# ospi_v13.net
KiCad netlist of a schematic drawn in EAGLE
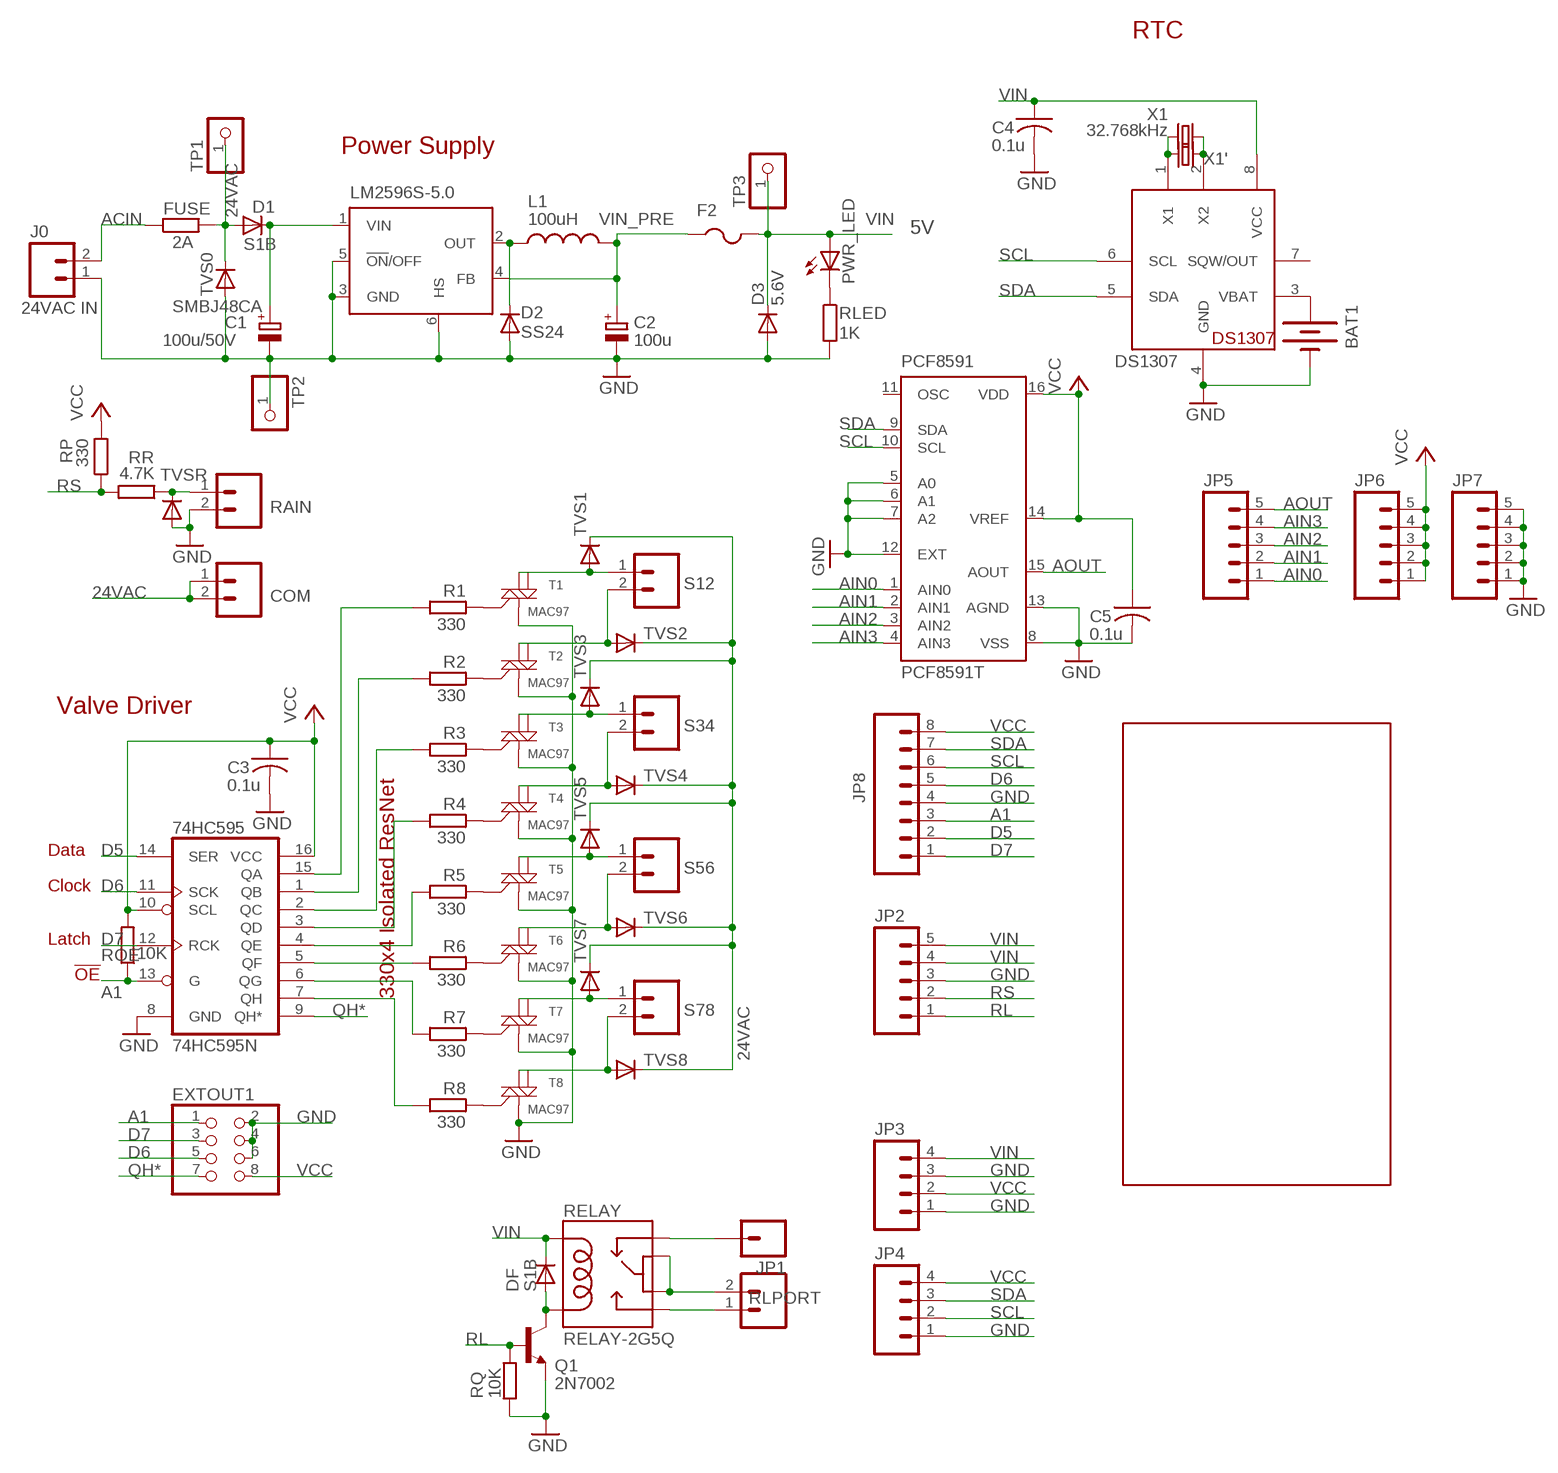
[diagram p0: schematic, sheet 1]

(export (version "E")
  (design (tool "Eeschema 10.0.6"))
  (components
    (comp (ref "74HC595")
      (value "74HC595N")
      (footprint "eagle-import:SO16")
      (libsource (lib "eagle-import") (part "74595DLS"))
    )
    (comp (ref "BAT1")
      (value "BATTERYBATTERY_12MM_SMT")
      (footprint "eagle-import:BATTCON_12MM_SMT")
      (libsource (lib "eagle-import") (part "BATTERYBATTERY_12MM_SMT"))
    )
    (comp (ref "C1")
      (value "100u/50V")
      (footprint "eagle-import:PANASONIC_E")
      (libsource (lib "eagle-import") (part "CPOL-EUE"))
    )
    (comp (ref "C2")
      (value "100u")
      (footprint "eagle-import:PANASONIC_E")
      (libsource (lib "eagle-import") (part "CPOL-EUE"))
    )
    (comp (ref "C3")
      (value "0.1u")
      (footprint "eagle-import:C0805K")
      (libsource (lib "eagle-import") (part "C-USC0805K"))
    )
    (comp (ref "C4")
      (value "0.1u")
      (footprint "eagle-import:C0805K")
      (libsource (lib "eagle-import") (part "C-USC0805K"))
    )
    (comp (ref "C5")
      (value "0.1u")
      (footprint "eagle-import:C0805K")
      (libsource (lib "eagle-import") (part "C-USC0805K"))
    )
    (comp (ref "COM")
      (value "M025MM-X")
      (footprint "eagle-import:SCREWTERMINAL-5MM-2-X")
      (libsource (lib "eagle-import") (part "M025MM-X"))
    )
    (comp (ref "D1")
      (value "S1B")
      (footprint "eagle-import:DO-214AC")
      (libsource (lib "eagle-import") (part "DIODE-DO-214AC"))
    )
    (comp (ref "D2")
      (value "SS24")
      (footprint "eagle-import:DO-214AC")
      (libsource (lib "eagle-import") (part "DIODE-DO-214AC"))
    )
    (comp (ref "D3")
      (value "5.6V")
      (footprint "eagle-import:MINIMELF")
      (libsource (lib "eagle-import") (part "DIODE-MINIMELF"))
    )
    (comp (ref "DF")
      (value "S1B")
      (footprint "eagle-import:DO-214AC")
      (libsource (lib "eagle-import") (part "DIODE-DO-214AC"))
    )
    (comp (ref "DS1307")
      (value "DS1307")
      (footprint "eagle-import:SO08")
      (libsource (lib "eagle-import") (part "DS1307SOIC"))
    )
    (comp (ref "EXTOUT1")
      (value "PINHD-2X4/90")
      (footprint "eagle-import:2X04_90")
      (libsource (lib "eagle-import") (part "PINHD-2X4/90"))
    )
    (comp (ref "F2")
      (value "PTCFUSE-1812")
      (footprint "eagle-import:1812")
      (libsource (lib "eagle-import") (part "PTCFUSE-1812"))
    )
    (comp (ref "FUSE")
      (value "2A")
      (footprint "eagle-import:0411_15")
      (libsource (lib "eagle-import") (part "R-EU_0411/15"))
    )
    (comp (ref "J0")
      (value "24VAC IN")
      (footprint "eagle-import:SCREWTERMINAL-4MM-2-X")
      (libsource (lib "eagle-import") (part "M024MM-X"))
    )
    (comp (ref "JP1")
      (value "M01PTH")
      (footprint "eagle-import:1X01")
      (libsource (lib "eagle-import") (part "M01PTH"))
    )
    (comp (ref "JP2")
      (value "M05LOCK")
      (footprint "eagle-import:1X05_LOCK")
      (libsource (lib "eagle-import") (part "M05LOCK"))
    )
    (comp (ref "JP3")
      (value "M04LOCK")
      (footprint "eagle-import:1X04_LOCK")
      (libsource (lib "eagle-import") (part "M04LOCK"))
    )
    (comp (ref "JP4")
      (value "M04LOCK")
      (footprint "eagle-import:1X04_LOCK")
      (libsource (lib "eagle-import") (part "M04LOCK"))
    )
    (comp (ref "JP5")
      (value "M05LOCK")
      (footprint "eagle-import:1X05_LOCK")
      (libsource (lib "eagle-import") (part "M05LOCK"))
    )
    (comp (ref "JP6")
      (value "M05LOCK")
      (footprint "eagle-import:1X05_LOCK")
      (libsource (lib "eagle-import") (part "M05LOCK"))
    )
    (comp (ref "JP7")
      (value "M05LOCK")
      (footprint "eagle-import:1X05_LOCK")
      (libsource (lib "eagle-import") (part "M05LOCK"))
    )
    (comp (ref "JP8")
      (value "M08LOCK")
      (footprint "eagle-import:1X08_LOCK")
      (libsource (lib "eagle-import") (part "M08LOCK"))
    )
    (comp (ref "L1")
      (value "100uH")
      (footprint "eagle-import:CDRH125")
      (libsource (lib "eagle-import") (part "INDUCTORPWR"))
    )
    (comp (ref "LM2596S-5.0")
      (value "LM2596S")
      (footprint "eagle-import:TO263-5")
      (fields (field (name "MF") "NATIONAL SEMICONDUCTOR") (field (name "MPN") "LM2596S-ADJ/NOPB"))
      (libsource (lib "eagle-import") (part "LM2596S"))
    )
    (comp (ref "PCF8591")
      (value "PCF8591T")
      (footprint "eagle-import:SO16W")
      (fields (field (name "MPN") "PCF8591T/2,512"))
      (libsource (lib "eagle-import") (part "PCF8591T"))
    )
    (comp (ref "PWR_LED")
      (value "LEDCHIPLED_0805")
      (footprint "eagle-import:CHIPLED_0805")
      (libsource (lib "eagle-import") (part "LEDCHIPLED_0805"))
    )
    (comp (ref "Q1")
      (value "2N7002")
      (footprint "eagle-import:SOT23-3")
      (libsource (lib "eagle-import") (part "TRANSISTOR_NPNSOT23-3"))
    )
    (comp (ref "R1")
      (value "330")
      (footprint "eagle-import:R0805")
      (libsource (lib "eagle-import") (part "R-EU_R0805"))
    )
    (comp (ref "R2")
      (value "330")
      (footprint "eagle-import:R0805")
      (libsource (lib "eagle-import") (part "R-EU_R0805"))
    )
    (comp (ref "R3")
      (value "330")
      (footprint "eagle-import:R0805")
      (libsource (lib "eagle-import") (part "R-EU_R0805"))
    )
    (comp (ref "R4")
      (value "330")
      (footprint "eagle-import:R0805")
      (libsource (lib "eagle-import") (part "R-EU_R0805"))
    )
    (comp (ref "R5")
      (value "330")
      (footprint "eagle-import:R0805")
      (libsource (lib "eagle-import") (part "R-EU_R0805"))
    )
    (comp (ref "R6")
      (value "330")
      (footprint "eagle-import:R0805")
      (libsource (lib "eagle-import") (part "R-EU_R0805"))
    )
    (comp (ref "R7")
      (value "330")
      (footprint "eagle-import:R0805")
      (libsource (lib "eagle-import") (part "R-EU_R0805"))
    )
    (comp (ref "R8")
      (value "330")
      (footprint "eagle-import:R0805")
      (libsource (lib "eagle-import") (part "R-EU_R0805"))
    )
    (comp (ref "RAIN")
      (value "M025MM-X")
      (footprint "eagle-import:SCREWTERMINAL-5MM-2-X")
      (libsource (lib "eagle-import") (part "M025MM-X"))
    )
    (comp (ref "RELAY")
      (value "RELAY-2G5Q")
      (footprint "eagle-import:RELAY-G5V")
      (libsource (lib "eagle-import") (part "RELAY-2G5Q"))
    )
    (comp (ref "RLED")
      (value "1K")
      (footprint "eagle-import:R0805")
      (libsource (lib "eagle-import") (part "R-EU_R0805"))
    )
    (comp (ref "RLPORT")
      (value "M025MM")
      (footprint "eagle-import:SCREWTERMINAL-5MM-2")
      (libsource (lib "eagle-import") (part "M025MM"))
    )
    (comp (ref "ROE")
      (value "10K")
      (footprint "eagle-import:R0805")
      (libsource (lib "eagle-import") (part "R-EU_R0805"))
    )
    (comp (ref "RP")
      (value "330")
      (footprint "eagle-import:R0805")
      (libsource (lib "eagle-import") (part "R-EU_R0805"))
    )
    (comp (ref "RQ")
      (value "10K")
      (footprint "eagle-import:R0805")
      (libsource (lib "eagle-import") (part "R-EU_R0805"))
    )
    (comp (ref "RR")
      (value "4.7K")
      (footprint "eagle-import:R0805")
      (libsource (lib "eagle-import") (part "R-EU_R0805"))
    )
    (comp (ref "S12")
      (value "M025MM-X")
      (footprint "eagle-import:SCREWTERMINAL-5MM-2-X")
      (libsource (lib "eagle-import") (part "M025MM-X"))
    )
    (comp (ref "S34")
      (value "M025MM-X")
      (footprint "eagle-import:SCREWTERMINAL-5MM-2-X")
      (libsource (lib "eagle-import") (part "M025MM-X"))
    )
    (comp (ref "S56")
      (value "M025MM-X")
      (footprint "eagle-import:SCREWTERMINAL-5MM-2-X")
      (libsource (lib "eagle-import") (part "M025MM-X"))
    )
    (comp (ref "S78")
      (value "M025MM-X")
      (footprint "eagle-import:SCREWTERMINAL-5MM-2-X")
      (libsource (lib "eagle-import") (part "M025MM-X"))
    )
    (comp (ref "T1")
      (value "MAC97")
      (footprint "eagle-import:SOT223")
      (libsource (lib "eagle-import") (part "MAC97SOT223"))
    )
    (comp (ref "T2")
      (value "MAC97")
      (footprint "eagle-import:SOT223")
      (libsource (lib "eagle-import") (part "MAC97SOT223"))
    )
    (comp (ref "T3")
      (value "MAC97")
      (footprint "eagle-import:SOT223")
      (libsource (lib "eagle-import") (part "MAC97SOT223"))
    )
    (comp (ref "T4")
      (value "MAC97")
      (footprint "eagle-import:SOT223")
      (libsource (lib "eagle-import") (part "MAC97SOT223"))
    )
    (comp (ref "T5")
      (value "MAC97")
      (footprint "eagle-import:SOT223")
      (libsource (lib "eagle-import") (part "MAC97SOT223"))
    )
    (comp (ref "T6")
      (value "MAC97")
      (footprint "eagle-import:SOT223")
      (libsource (lib "eagle-import") (part "MAC97SOT223"))
    )
    (comp (ref "T7")
      (value "MAC97")
      (footprint "eagle-import:SOT223")
      (libsource (lib "eagle-import") (part "MAC97SOT223"))
    )
    (comp (ref "T8")
      (value "MAC97")
      (footprint "eagle-import:SOT223")
      (libsource (lib "eagle-import") (part "MAC97SOT223"))
    )
    (comp (ref "TP1")
      (value "PINHD-1X1CB")
      (footprint "eagle-import:1X01-CLEANBIG")
      (libsource (lib "eagle-import") (part "PINHD-1X1CB"))
    )
    (comp (ref "TP2")
      (value "PINHD-1X1CB")
      (footprint "eagle-import:1X01-CLEANBIG")
      (libsource (lib "eagle-import") (part "PINHD-1X1CB"))
    )
    (comp (ref "TP3")
      (value "PINHD-1X1CB")
      (footprint "eagle-import:1X01-CLEANBIG")
      (libsource (lib "eagle-import") (part "PINHD-1X1CB"))
    )
    (comp (ref "TVS0")
      (value "SMBJ48CA")
      (footprint "eagle-import:SMB")
      (libsource (lib "eagle-import") (part "DIODE-SMB"))
    )
    (comp (ref "TVS1")
      (value "DIODE-SMB")
      (footprint "eagle-import:SMB")
      (libsource (lib "eagle-import") (part "DIODE-SMB"))
    )
    (comp (ref "TVS2")
      (value "DIODE-SMB")
      (footprint "eagle-import:SMB")
      (libsource (lib "eagle-import") (part "DIODE-SMB"))
    )
    (comp (ref "TVS3")
      (value "DIODE-SMB")
      (footprint "eagle-import:SMB")
      (libsource (lib "eagle-import") (part "DIODE-SMB"))
    )
    (comp (ref "TVS4")
      (value "DIODE-SMB")
      (footprint "eagle-import:SMB")
      (libsource (lib "eagle-import") (part "DIODE-SMB"))
    )
    (comp (ref "TVS5")
      (value "DIODE-SMB")
      (footprint "eagle-import:SMB")
      (libsource (lib "eagle-import") (part "DIODE-SMB"))
    )
    (comp (ref "TVS6")
      (value "DIODE-SMB")
      (footprint "eagle-import:SMB")
      (libsource (lib "eagle-import") (part "DIODE-SMB"))
    )
    (comp (ref "TVS7")
      (value "DIODE-SMB")
      (footprint "eagle-import:SMB")
      (libsource (lib "eagle-import") (part "DIODE-SMB"))
    )
    (comp (ref "TVS8")
      (value "DIODE-SMB")
      (footprint "eagle-import:SMB")
      (libsource (lib "eagle-import") (part "DIODE-SMB"))
    )
    (comp (ref "TVSR")
      (value "DIODE-SMB")
      (footprint "eagle-import:SMB")
      (libsource (lib "eagle-import") (part "DIODE-SMB"))
    )
    (comp (ref "U$2")
      (value "OSPI")
      (footprint "eagle-import:OSPI")
      (libsource (lib "eagle-import") (part "OSPI"))
    )
    (comp (ref "X1")
      (value "32.768kHz")
      (footprint "eagle-import:MM20SS")
      (libsource (lib "eagle-import") (part "CRYSTALMM20SS"))
    )
    (comp (ref "X1'")
      (value "32.768kHz")
      (footprint "eagle-import:TC38H")
      (libsource (lib "eagle-import") (part "CRYSTALTC38H"))
    )
  )
  (nets
    (net (code "1") (name "/24VAC") (class "Default")
      (node (ref "COM") (pin "1") (pinfunction "1_1") (pintype "passive"))
      (node (ref "COM") (pin "2") (pinfunction "2_2") (pintype "passive"))
      (node (ref "D1") (pin "A") (pinfunction "A_A") (pintype "passive"))
      (node (ref "FUSE") (pin "2") (pinfunction "2_2") (pintype "passive"))
      (node (ref "TP1") (pin "1") (pinfunction "1_1") (pintype "passive"))
      (node (ref "TVS0") (pin "C") (pinfunction "C_C") (pintype "passive"))
      (node (ref "TVS1") (pin "C") (pinfunction "C_C") (pintype "passive"))
      (node (ref "TVS2") (pin "C") (pinfunction "C_C") (pintype "passive"))
      (node (ref "TVS3") (pin "C") (pinfunction "C_C") (pintype "passive"))
      (node (ref "TVS4") (pin "C") (pinfunction "C_C") (pintype "passive"))
      (node (ref "TVS5") (pin "C") (pinfunction "C_C") (pintype "passive"))
      (node (ref "TVS6") (pin "C") (pinfunction "C_C") (pintype "passive"))
      (node (ref "TVS7") (pin "C") (pinfunction "C_C") (pintype "passive"))
      (node (ref "TVS8") (pin "C") (pinfunction "C_C") (pintype "passive"))
    )
    (net (code "2") (name "/A1") (class "Default")
      (node (ref "74HC595") (pin "13") (pinfunction "G_13") (pintype "input"))
      (node (ref "EXTOUT1") (pin "1") (pinfunction "1_1") (pintype "passive"))
      (node (ref "JP8") (pin "3") (pinfunction "3_3") (pintype "passive"))
      (node (ref "ROE") (pin "1") (pinfunction "1_1") (pintype "passive"))
    )
    (net (code "3") (name "/ACIN") (class "Default")
      (node (ref "FUSE") (pin "1") (pinfunction "1_1") (pintype "passive"))
      (node (ref "J0") (pin "2") (pinfunction "2_2") (pintype "passive"))
    )
    (net (code "4") (name "/AIN0") (class "Default")
      (node (ref "JP5") (pin "1") (pinfunction "1_1") (pintype "passive"))
      (node (ref "PCF8591") (pin "1") (pinfunction "AIN0_1") (pintype "input"))
    )
    (net (code "5") (name "/AIN1") (class "Default")
      (node (ref "JP5") (pin "2") (pinfunction "2_2") (pintype "passive"))
      (node (ref "PCF8591") (pin "2") (pinfunction "AIN1_2") (pintype "input"))
    )
    (net (code "6") (name "/AIN2") (class "Default")
      (node (ref "JP5") (pin "3") (pinfunction "3_3") (pintype "passive"))
      (node (ref "PCF8591") (pin "3") (pinfunction "AIN2_3") (pintype "input"))
    )
    (net (code "7") (name "/AIN3") (class "Default")
      (node (ref "JP5") (pin "4") (pinfunction "4_4") (pintype "passive"))
      (node (ref "PCF8591") (pin "4") (pinfunction "AIN3_4") (pintype "input"))
    )
    (net (code "8") (name "/AOUT") (class "Default")
      (node (ref "JP5") (pin "5") (pinfunction "5_5") (pintype "passive"))
      (node (ref "PCF8591") (pin "15") (pinfunction "AOUT_15") (pintype "output"))
    )
    (net (code "9") (name "/D5") (class "Default")
      (node (ref "74HC595") (pin "14") (pinfunction "SER_14") (pintype "input"))
      (node (ref "JP8") (pin "2") (pinfunction "2_2") (pintype "passive"))
    )
    (net (code "10") (name "/D6") (class "Default")
      (node (ref "74HC595") (pin "11") (pinfunction "SCK_11") (pintype "input"))
      (node (ref "EXTOUT1") (pin "5") (pinfunction "5_5") (pintype "passive"))
      (node (ref "JP8") (pin "5") (pinfunction "5_5") (pintype "passive"))
    )
    (net (code "11") (name "/D7") (class "Default")
      (node (ref "74HC595") (pin "12") (pinfunction "RCK_12") (pintype "input"))
      (node (ref "EXTOUT1") (pin "3") (pinfunction "3_3") (pintype "passive"))
      (node (ref "JP8") (pin "1") (pinfunction "1_1") (pintype "passive"))
    )
    (net (code "12") (name "/QH*") (class "Default")
      (node (ref "74HC595") (pin "9") (pinfunction "QH*_9") (pintype "tri_state"))
      (node (ref "EXTOUT1") (pin "7") (pinfunction "7_7") (pintype "passive"))
    )
    (net (code "13") (name "/RL") (class "Default")
      (node (ref "JP2") (pin "1") (pinfunction "1_1") (pintype "passive"))
      (node (ref "Q1") (pin "1") (pinfunction "B_1") (pintype "passive"))
      (node (ref "RQ") (pin "1") (pinfunction "1_1") (pintype "passive"))
    )
    (net (code "14") (name "/RS") (class "Default")
      (node (ref "JP2") (pin "2") (pinfunction "2_2") (pintype "passive"))
      (node (ref "RP") (pin "1") (pinfunction "1_1") (pintype "passive"))
      (node (ref "RR") (pin "2") (pinfunction "2_2") (pintype "passive"))
    )
    (net (code "15") (name "/SCL") (class "Default")
      (node (ref "DS1307") (pin "6") (pinfunction "SCL_6") (pintype "bidirectional"))
      (node (ref "JP4") (pin "2") (pinfunction "2_2") (pintype "passive"))
      (node (ref "JP8") (pin "6") (pinfunction "6_6") (pintype "passive"))
      (node (ref "PCF8591") (pin "10") (pinfunction "SCL_10") (pintype "input"))
    )
    (net (code "16") (name "/SDA") (class "Default")
      (node (ref "DS1307") (pin "5") (pinfunction "SDA_5") (pintype "bidirectional"))
      (node (ref "JP4") (pin "3") (pinfunction "3_3") (pintype "passive"))
      (node (ref "JP8") (pin "7") (pinfunction "7_7") (pintype "passive"))
      (node (ref "PCF8591") (pin "9") (pinfunction "SDA_9") (pintype "bidirectional"))
    )
    (net (code "17") (name "/VIN") (class "Default")
      (node (ref "C4") (pin "1") (pinfunction "1_1") (pintype "passive"))
      (node (ref "D3") (pin "C") (pinfunction "C_C") (pintype "passive"))
      (node (ref "DF") (pin "C") (pinfunction "C_C") (pintype "passive"))
      (node (ref "DS1307") (pin "8") (pinfunction "VCC_8") (pintype "power_in"))
      (node (ref "F2") (pin "2") (pinfunction "2_2") (pintype "passive"))
      (node (ref "JP2") (pin "4") (pinfunction "4_4") (pintype "passive"))
      (node (ref "JP2") (pin "5") (pinfunction "5_5") (pintype "passive"))
      (node (ref "JP3") (pin "4") (pinfunction "4_4") (pintype "passive"))
      (node (ref "PWR_LED") (pin "A") (pinfunction "A_A") (pintype "passive"))
      (node (ref "RELAY") (pin "2") (pinfunction "2_2") (pintype "bidirectional"))
      (node (ref "TP3") (pin "1") (pinfunction "1_1") (pintype "passive"))
    )
    (net (code "18") (name "/VIN_PRE") (class "Default")
      (node (ref "C2") (pin "+") (pinfunction "+_+") (pintype "passive"))
      (node (ref "F2") (pin "1") (pinfunction "1_1") (pintype "passive"))
      (node (ref "L1") (pin "2") (pinfunction "2_2") (pintype "passive"))
      (node (ref "LM2596S-5.0") (pin "4") (pinfunction "FB_4") (pintype "input"))
    )
    (net (code "19") (name "GND") (class "Default")
      (node (ref "74HC595") (pin "8") (pinfunction "GND_8") (pintype "power_in"))
      (node (ref "BAT1") (pin "P$1") (pinfunction "-_P$1") (pintype "power_in"))
      (node (ref "C1") (pin "-") (pinfunction "-_-") (pintype "passive"))
      (node (ref "C2") (pin "-") (pinfunction "-_-") (pintype "passive"))
      (node (ref "C3") (pin "2") (pinfunction "2_2") (pintype "passive"))
      (node (ref "C4") (pin "2") (pinfunction "2_2") (pintype "passive"))
      (node (ref "C5") (pin "2") (pinfunction "2_2") (pintype "passive"))
      (node (ref "D2") (pin "A") (pinfunction "A_A") (pintype "passive"))
      (node (ref "D3") (pin "A") (pinfunction "A_A") (pintype "passive"))
      (node (ref "DS1307") (pin "4") (pinfunction "GND_4") (pintype "power_in"))
      (node (ref "EXTOUT1") (pin "2") (pinfunction "2_2") (pintype "passive"))
      (node (ref "EXTOUT1") (pin "4") (pinfunction "4_4") (pintype "passive"))
      (node (ref "EXTOUT1") (pin "6") (pinfunction "6_6") (pintype "passive"))
      (node (ref "J0") (pin "1") (pinfunction "1_1") (pintype "passive"))
      (node (ref "JP2") (pin "3") (pinfunction "3_3") (pintype "passive"))
      (node (ref "JP3") (pin "1") (pinfunction "1_1") (pintype "passive"))
      (node (ref "JP3") (pin "3") (pinfunction "3_3") (pintype "passive"))
      (node (ref "JP4") (pin "1") (pinfunction "1_1") (pintype "passive"))
      (node (ref "JP7") (pin "1") (pinfunction "1_1") (pintype "passive"))
      (node (ref "JP7") (pin "2") (pinfunction "2_2") (pintype "passive"))
      (node (ref "JP7") (pin "3") (pinfunction "3_3") (pintype "passive"))
      (node (ref "JP7") (pin "4") (pinfunction "4_4") (pintype "passive"))
      (node (ref "JP7") (pin "5") (pinfunction "5_5") (pintype "passive"))
      (node (ref "JP8") (pin "4") (pinfunction "4_4") (pintype "passive"))
      (node (ref "LM2596S-5.0") (pin "3") (pinfunction "GND_3") (pintype "power_in"))
      (node (ref "LM2596S-5.0") (pin "5") (pinfunction "~{ON}/OFF_5") (pintype "input"))
      (node (ref "LM2596S-5.0") (pin "6") (pinfunction "HS_6") (pintype "power_in"))
      (node (ref "PCF8591") (pin "12") (pinfunction "EXT_12") (pintype "input"))
      (node (ref "PCF8591") (pin "13") (pinfunction "AGND_13") (pintype "power_in"))
      (node (ref "PCF8591") (pin "5") (pinfunction "A0_5") (pintype "input"))
      (node (ref "PCF8591") (pin "6") (pinfunction "A1_6") (pintype "input"))
      (node (ref "PCF8591") (pin "7") (pinfunction "A2_7") (pintype "input"))
      (node (ref "PCF8591") (pin "8") (pinfunction "VSS_8") (pintype "power_in"))
      (node (ref "Q1") (pin "2") (pinfunction "E_2") (pintype "passive"))
      (node (ref "RAIN") (pin "2") (pinfunction "2_2") (pintype "passive"))
      (node (ref "RLED") (pin "2") (pinfunction "2_2") (pintype "passive"))
      (node (ref "RQ") (pin "2") (pinfunction "2_2") (pintype "passive"))
      (node (ref "T1") (pin "1") (pinfunction "M1_1") (pintype "bidirectional"))
      (node (ref "T2") (pin "1") (pinfunction "M1_1") (pintype "bidirectional"))
      (node (ref "T3") (pin "1") (pinfunction "M1_1") (pintype "bidirectional"))
      (node (ref "T4") (pin "1") (pinfunction "M1_1") (pintype "bidirectional"))
      (node (ref "T5") (pin "1") (pinfunction "M1_1") (pintype "bidirectional"))
      (node (ref "T6") (pin "1") (pinfunction "M1_1") (pintype "bidirectional"))
      (node (ref "T7") (pin "1") (pinfunction "M1_1") (pintype "bidirectional"))
      (node (ref "T8") (pin "1") (pinfunction "M1_1") (pintype "bidirectional"))
      (node (ref "TP2") (pin "1") (pinfunction "1_1") (pintype "passive"))
      (node (ref "TVS0") (pin "A") (pinfunction "A_A") (pintype "passive"))
      (node (ref "TVSR") (pin "A") (pinfunction "A_A") (pintype "passive"))
    )
    (net (code "20") (name "Net-(74HC595-QA)") (class "Default")
      (node (ref "74HC595") (pin "15") (pinfunction "QA_15") (pintype "tri_state"))
      (node (ref "R1") (pin "1") (pinfunction "1_1") (pintype "passive"))
    )
    (net (code "21") (name "Net-(74HC595-QB)") (class "Default")
      (node (ref "74HC595") (pin "1") (pinfunction "QB_1") (pintype "tri_state"))
      (node (ref "R2") (pin "1") (pinfunction "1_1") (pintype "passive"))
    )
    (net (code "22") (name "Net-(74HC595-QC)") (class "Default")
      (node (ref "74HC595") (pin "2") (pinfunction "QC_2") (pintype "tri_state"))
      (node (ref "R3") (pin "1") (pinfunction "1_1") (pintype "passive"))
    )
    (net (code "23") (name "Net-(74HC595-QD)") (class "Default")
      (node (ref "74HC595") (pin "3") (pinfunction "QD_3") (pintype "tri_state"))
      (node (ref "R4") (pin "1") (pinfunction "1_1") (pintype "passive"))
    )
    (net (code "24") (name "Net-(74HC595-QE)") (class "Default")
      (node (ref "74HC595") (pin "4") (pinfunction "QE_4") (pintype "tri_state"))
      (node (ref "R5") (pin "1") (pinfunction "1_1") (pintype "passive"))
    )
    (net (code "25") (name "Net-(74HC595-QF)") (class "Default")
      (node (ref "74HC595") (pin "5") (pinfunction "QF_5") (pintype "tri_state"))
      (node (ref "R6") (pin "1") (pinfunction "1_1") (pintype "passive"))
    )
    (net (code "26") (name "Net-(74HC595-QG)") (class "Default")
      (node (ref "74HC595") (pin "6") (pinfunction "QG_6") (pintype "tri_state"))
      (node (ref "R7") (pin "1") (pinfunction "1_1") (pintype "passive"))
    )
    (net (code "27") (name "Net-(74HC595-QH)") (class "Default")
      (node (ref "74HC595") (pin "7") (pinfunction "QH_7") (pintype "tri_state"))
      (node (ref "R8") (pin "1") (pinfunction "1_1") (pintype "passive"))
    )
    (net (code "28") (name "Net-(BAT1-+)") (class "Default")
      (node (ref "BAT1") (pin "P$2") (pinfunction "+_P$2") (pintype "power_in"))
      (node (ref "DS1307") (pin "3") (pinfunction "VBAT_3") (pintype "power_in"))
    )
    (net (code "29") (name "Net-(DS1307-X1)") (class "Default")
      (node (ref "DS1307") (pin "1") (pinfunction "X1_1") (pintype "passive"))
      (node (ref "X1") (pin "1") (pinfunction "1_1") (pintype "passive"))
      (node (ref "X1'") (pin "2") (pinfunction "2_2") (pintype "passive"))
    )
    (net (code "30") (name "Net-(DS1307-X2)") (class "Default")
      (node (ref "DS1307") (pin "2") (pinfunction "X2_2") (pintype "passive"))
      (node (ref "X1") (pin "4") (pinfunction "2_4") (pintype "passive"))
      (node (ref "X1'") (pin "1") (pinfunction "1_1") (pintype "passive"))
    )
    (net (code "31") (name "Net-(JP1-Pad1)") (class "Default")
      (node (ref "JP1") (pin "1") (pinfunction "1_1") (pintype "passive"))
      (node (ref "RELAY") (pin "1") (pinfunction "1_1") (pintype "bidirectional"))
    )
    (net (code "32") (name "Net-(LM2596S-5.0-OUT)") (class "Default")
      (node (ref "D2") (pin "C") (pinfunction "C_C") (pintype "passive"))
      (node (ref "L1") (pin "1") (pinfunction "1_1") (pintype "passive"))
      (node (ref "LM2596S-5.0") (pin "2") (pinfunction "OUT_2") (pintype "output"))
    )
    (net (code "33") (name "Net-(LM2596S-5.0-VIN)") (class "Default")
      (node (ref "C1") (pin "+") (pinfunction "+_+") (pintype "passive"))
      (node (ref "D1") (pin "C") (pinfunction "C_C") (pintype "passive"))
      (node (ref "LM2596S-5.0") (pin "1") (pinfunction "VIN_1") (pintype "input"))
    )
    (net (code "34") (name "Net-(PWR_LED-PadC)") (class "Default")
      (node (ref "PWR_LED") (pin "C") (pinfunction "C_C") (pintype "passive"))
      (node (ref "RLED") (pin "1") (pinfunction "1_1") (pintype "passive"))
    )
    (net (code "35") (name "Net-(Q1-C)") (class "Default")
      (node (ref "DF") (pin "A") (pinfunction "A_A") (pintype "passive"))
      (node (ref "Q1") (pin "3") (pinfunction "C_3") (pintype "passive"))
      (node (ref "RELAY") (pin "9") (pinfunction "9_9") (pintype "bidirectional"))
    )
    (net (code "36") (name "Net-(RAIN-Pad1)") (class "Default")
      (node (ref "RAIN") (pin "1") (pinfunction "1_1") (pintype "passive"))
      (node (ref "RR") (pin "1") (pinfunction "1_1") (pintype "passive"))
      (node (ref "TVSR") (pin "C") (pinfunction "C_C") (pintype "passive"))
    )
    (net (code "37") (name "Net-(RELAY-Pad5)") (class "Default")
      (node (ref "RELAY") (pin "5") (pinfunction "5_5") (pintype "bidirectional"))
      (node (ref "RELAY") (pin "6") (pinfunction "6_6") (pintype "bidirectional"))
      (node (ref "RLPORT") (pin "2") (pinfunction "2_2") (pintype "passive"))
    )
    (net (code "38") (name "Net-(RELAY-Pad10)") (class "Default")
      (node (ref "RELAY") (pin "10") (pinfunction "10_10") (pintype "bidirectional"))
      (node (ref "RLPORT") (pin "1") (pinfunction "1_1") (pintype "passive"))
    )
    (net (code "39") (name "Net-(T1-G)") (class "Default")
      (node (ref "R1") (pin "2") (pinfunction "2_2") (pintype "passive"))
      (node (ref "T1") (pin "3") (pinfunction "G_3") (pintype "bidirectional"))
    )
    (net (code "40") (name "Net-(T1-M2)") (class "Default")
      (node (ref "S12") (pin "1") (pinfunction "1_1") (pintype "passive"))
      (node (ref "T1") (pin "2") (pinfunction "M2_2") (pintype "bidirectional"))
      (node (ref "TVS1") (pin "A") (pinfunction "A_A") (pintype "passive"))
    )
    (net (code "41") (name "Net-(T2-G)") (class "Default")
      (node (ref "R2") (pin "2") (pinfunction "2_2") (pintype "passive"))
      (node (ref "T2") (pin "3") (pinfunction "G_3") (pintype "bidirectional"))
    )
    (net (code "42") (name "Net-(T2-M2)") (class "Default")
      (node (ref "S12") (pin "2") (pinfunction "2_2") (pintype "passive"))
      (node (ref "T2") (pin "2") (pinfunction "M2_2") (pintype "bidirectional"))
      (node (ref "TVS2") (pin "A") (pinfunction "A_A") (pintype "passive"))
    )
    (net (code "43") (name "Net-(T3-G)") (class "Default")
      (node (ref "R3") (pin "2") (pinfunction "2_2") (pintype "passive"))
      (node (ref "T3") (pin "3") (pinfunction "G_3") (pintype "bidirectional"))
    )
    (net (code "44") (name "Net-(T3-M2)") (class "Default")
      (node (ref "S34") (pin "1") (pinfunction "1_1") (pintype "passive"))
      (node (ref "T3") (pin "2") (pinfunction "M2_2") (pintype "bidirectional"))
      (node (ref "TVS3") (pin "A") (pinfunction "A_A") (pintype "passive"))
    )
    (net (code "45") (name "Net-(T4-G)") (class "Default")
      (node (ref "R4") (pin "2") (pinfunction "2_2") (pintype "passive"))
      (node (ref "T4") (pin "3") (pinfunction "G_3") (pintype "bidirectional"))
    )
    (net (code "46") (name "Net-(T4-M2)") (class "Default")
      (node (ref "S34") (pin "2") (pinfunction "2_2") (pintype "passive"))
      (node (ref "T4") (pin "2") (pinfunction "M2_2") (pintype "bidirectional"))
      (node (ref "TVS4") (pin "A") (pinfunction "A_A") (pintype "passive"))
    )
    (net (code "47") (name "Net-(T5-G)") (class "Default")
      (node (ref "R5") (pin "2") (pinfunction "2_2") (pintype "passive"))
      (node (ref "T5") (pin "3") (pinfunction "G_3") (pintype "bidirectional"))
    )
    (net (code "48") (name "Net-(T5-M2)") (class "Default")
      (node (ref "S56") (pin "1") (pinfunction "1_1") (pintype "passive"))
      (node (ref "T5") (pin "2") (pinfunction "M2_2") (pintype "bidirectional"))
      (node (ref "TVS5") (pin "A") (pinfunction "A_A") (pintype "passive"))
    )
    (net (code "49") (name "Net-(T6-G)") (class "Default")
      (node (ref "R6") (pin "2") (pinfunction "2_2") (pintype "passive"))
      (node (ref "T6") (pin "3") (pinfunction "G_3") (pintype "bidirectional"))
    )
    (net (code "50") (name "Net-(T6-M2)") (class "Default")
      (node (ref "S56") (pin "2") (pinfunction "2_2") (pintype "passive"))
      (node (ref "T6") (pin "2") (pinfunction "M2_2") (pintype "bidirectional"))
      (node (ref "TVS6") (pin "A") (pinfunction "A_A") (pintype "passive"))
    )
    (net (code "51") (name "Net-(T7-G)") (class "Default")
      (node (ref "R7") (pin "2") (pinfunction "2_2") (pintype "passive"))
      (node (ref "T7") (pin "3") (pinfunction "G_3") (pintype "bidirectional"))
    )
    (net (code "52") (name "Net-(T7-M2)") (class "Default")
      (node (ref "S78") (pin "1") (pinfunction "1_1") (pintype "passive"))
      (node (ref "T7") (pin "2") (pinfunction "M2_2") (pintype "bidirectional"))
      (node (ref "TVS7") (pin "A") (pinfunction "A_A") (pintype "passive"))
    )
    (net (code "53") (name "Net-(T8-G)") (class "Default")
      (node (ref "R8") (pin "2") (pinfunction "2_2") (pintype "passive"))
      (node (ref "T8") (pin "3") (pinfunction "G_3") (pintype "bidirectional"))
    )
    (net (code "54") (name "Net-(T8-M2)") (class "Default")
      (node (ref "S78") (pin "2") (pinfunction "2_2") (pintype "passive"))
      (node (ref "T8") (pin "2") (pinfunction "M2_2") (pintype "bidirectional"))
      (node (ref "TVS8") (pin "A") (pinfunction "A_A") (pintype "passive"))
    )
    (net (code "55") (name "VCC") (class "Default")
      (node (ref "74HC595") (pin "10") (pinfunction "SCL_10") (pintype "input"))
      (node (ref "74HC595") (pin "16") (pinfunction "VCC_16") (pintype "power_in"))
      (node (ref "C3") (pin "1") (pinfunction "1_1") (pintype "passive"))
      (node (ref "C5") (pin "1") (pinfunction "1_1") (pintype "passive"))
      (node (ref "EXTOUT1") (pin "8") (pinfunction "8_8") (pintype "passive"))
      (node (ref "JP3") (pin "2") (pinfunction "2_2") (pintype "passive"))
      (node (ref "JP4") (pin "4") (pinfunction "4_4") (pintype "passive"))
      (node (ref "JP6") (pin "1") (pinfunction "1_1") (pintype "passive"))
      (node (ref "JP6") (pin "2") (pinfunction "2_2") (pintype "passive"))
      (node (ref "JP6") (pin "3") (pinfunction "3_3") (pintype "passive"))
      (node (ref "JP6") (pin "4") (pinfunction "4_4") (pintype "passive"))
      (node (ref "JP6") (pin "5") (pinfunction "5_5") (pintype "passive"))
      (node (ref "JP8") (pin "8") (pinfunction "8_8") (pintype "passive"))
      (node (ref "PCF8591") (pin "14") (pinfunction "VREF_14") (pintype "input"))
      (node (ref "PCF8591") (pin "16") (pinfunction "VDD_16") (pintype "power_in"))
      (node (ref "ROE") (pin "2") (pinfunction "2_2") (pintype "passive"))
      (node (ref "RP") (pin "2") (pinfunction "2_2") (pintype "passive"))
    )
    (net (code "56") (name "unconnected-(DS1307-SQW{slash}OUT-Pad7)") (class "Default")
      (node (ref "DS1307") (pin "7") (pinfunction "SQW/OUT_7") (pintype "bidirectional"))
    )
    (net (code "57") (name "unconnected-(PCF8591-OSC-Pad11)") (class "Default")
      (node (ref "PCF8591") (pin "11") (pinfunction "OSC_11") (pintype "input"))
    )
    (net (code "58") (name "unconnected-(T1-M2-4-Pad4)") (class "Default")
      (node (ref "T1") (pin "4") (pinfunction "M2-4_4") (pintype "bidirectional"))
    )
    (net (code "59") (name "unconnected-(T2-M2-4-Pad4)") (class "Default")
      (node (ref "T2") (pin "4") (pinfunction "M2-4_4") (pintype "bidirectional"))
    )
    (net (code "60") (name "unconnected-(T3-M2-4-Pad4)") (class "Default")
      (node (ref "T3") (pin "4") (pinfunction "M2-4_4") (pintype "bidirectional"))
    )
    (net (code "61") (name "unconnected-(T4-M2-4-Pad4)") (class "Default")
      (node (ref "T4") (pin "4") (pinfunction "M2-4_4") (pintype "bidirectional"))
    )
    (net (code "62") (name "unconnected-(T5-M2-4-Pad4)") (class "Default")
      (node (ref "T5") (pin "4") (pinfunction "M2-4_4") (pintype "bidirectional"))
    )
    (net (code "63") (name "unconnected-(T6-M2-4-Pad4)") (class "Default")
      (node (ref "T6") (pin "4") (pinfunction "M2-4_4") (pintype "bidirectional"))
    )
    (net (code "64") (name "unconnected-(T7-M2-4-Pad4)") (class "Default")
      (node (ref "T7") (pin "4") (pinfunction "M2-4_4") (pintype "bidirectional"))
    )
    (net (code "65") (name "unconnected-(T8-M2-4-Pad4)") (class "Default")
      (node (ref "T8") (pin "4") (pinfunction "M2-4_4") (pintype "bidirectional"))
    )
  )
)
